# DAC_1CH.net
KiCad netlist of a schematic drawn in Altium Designer
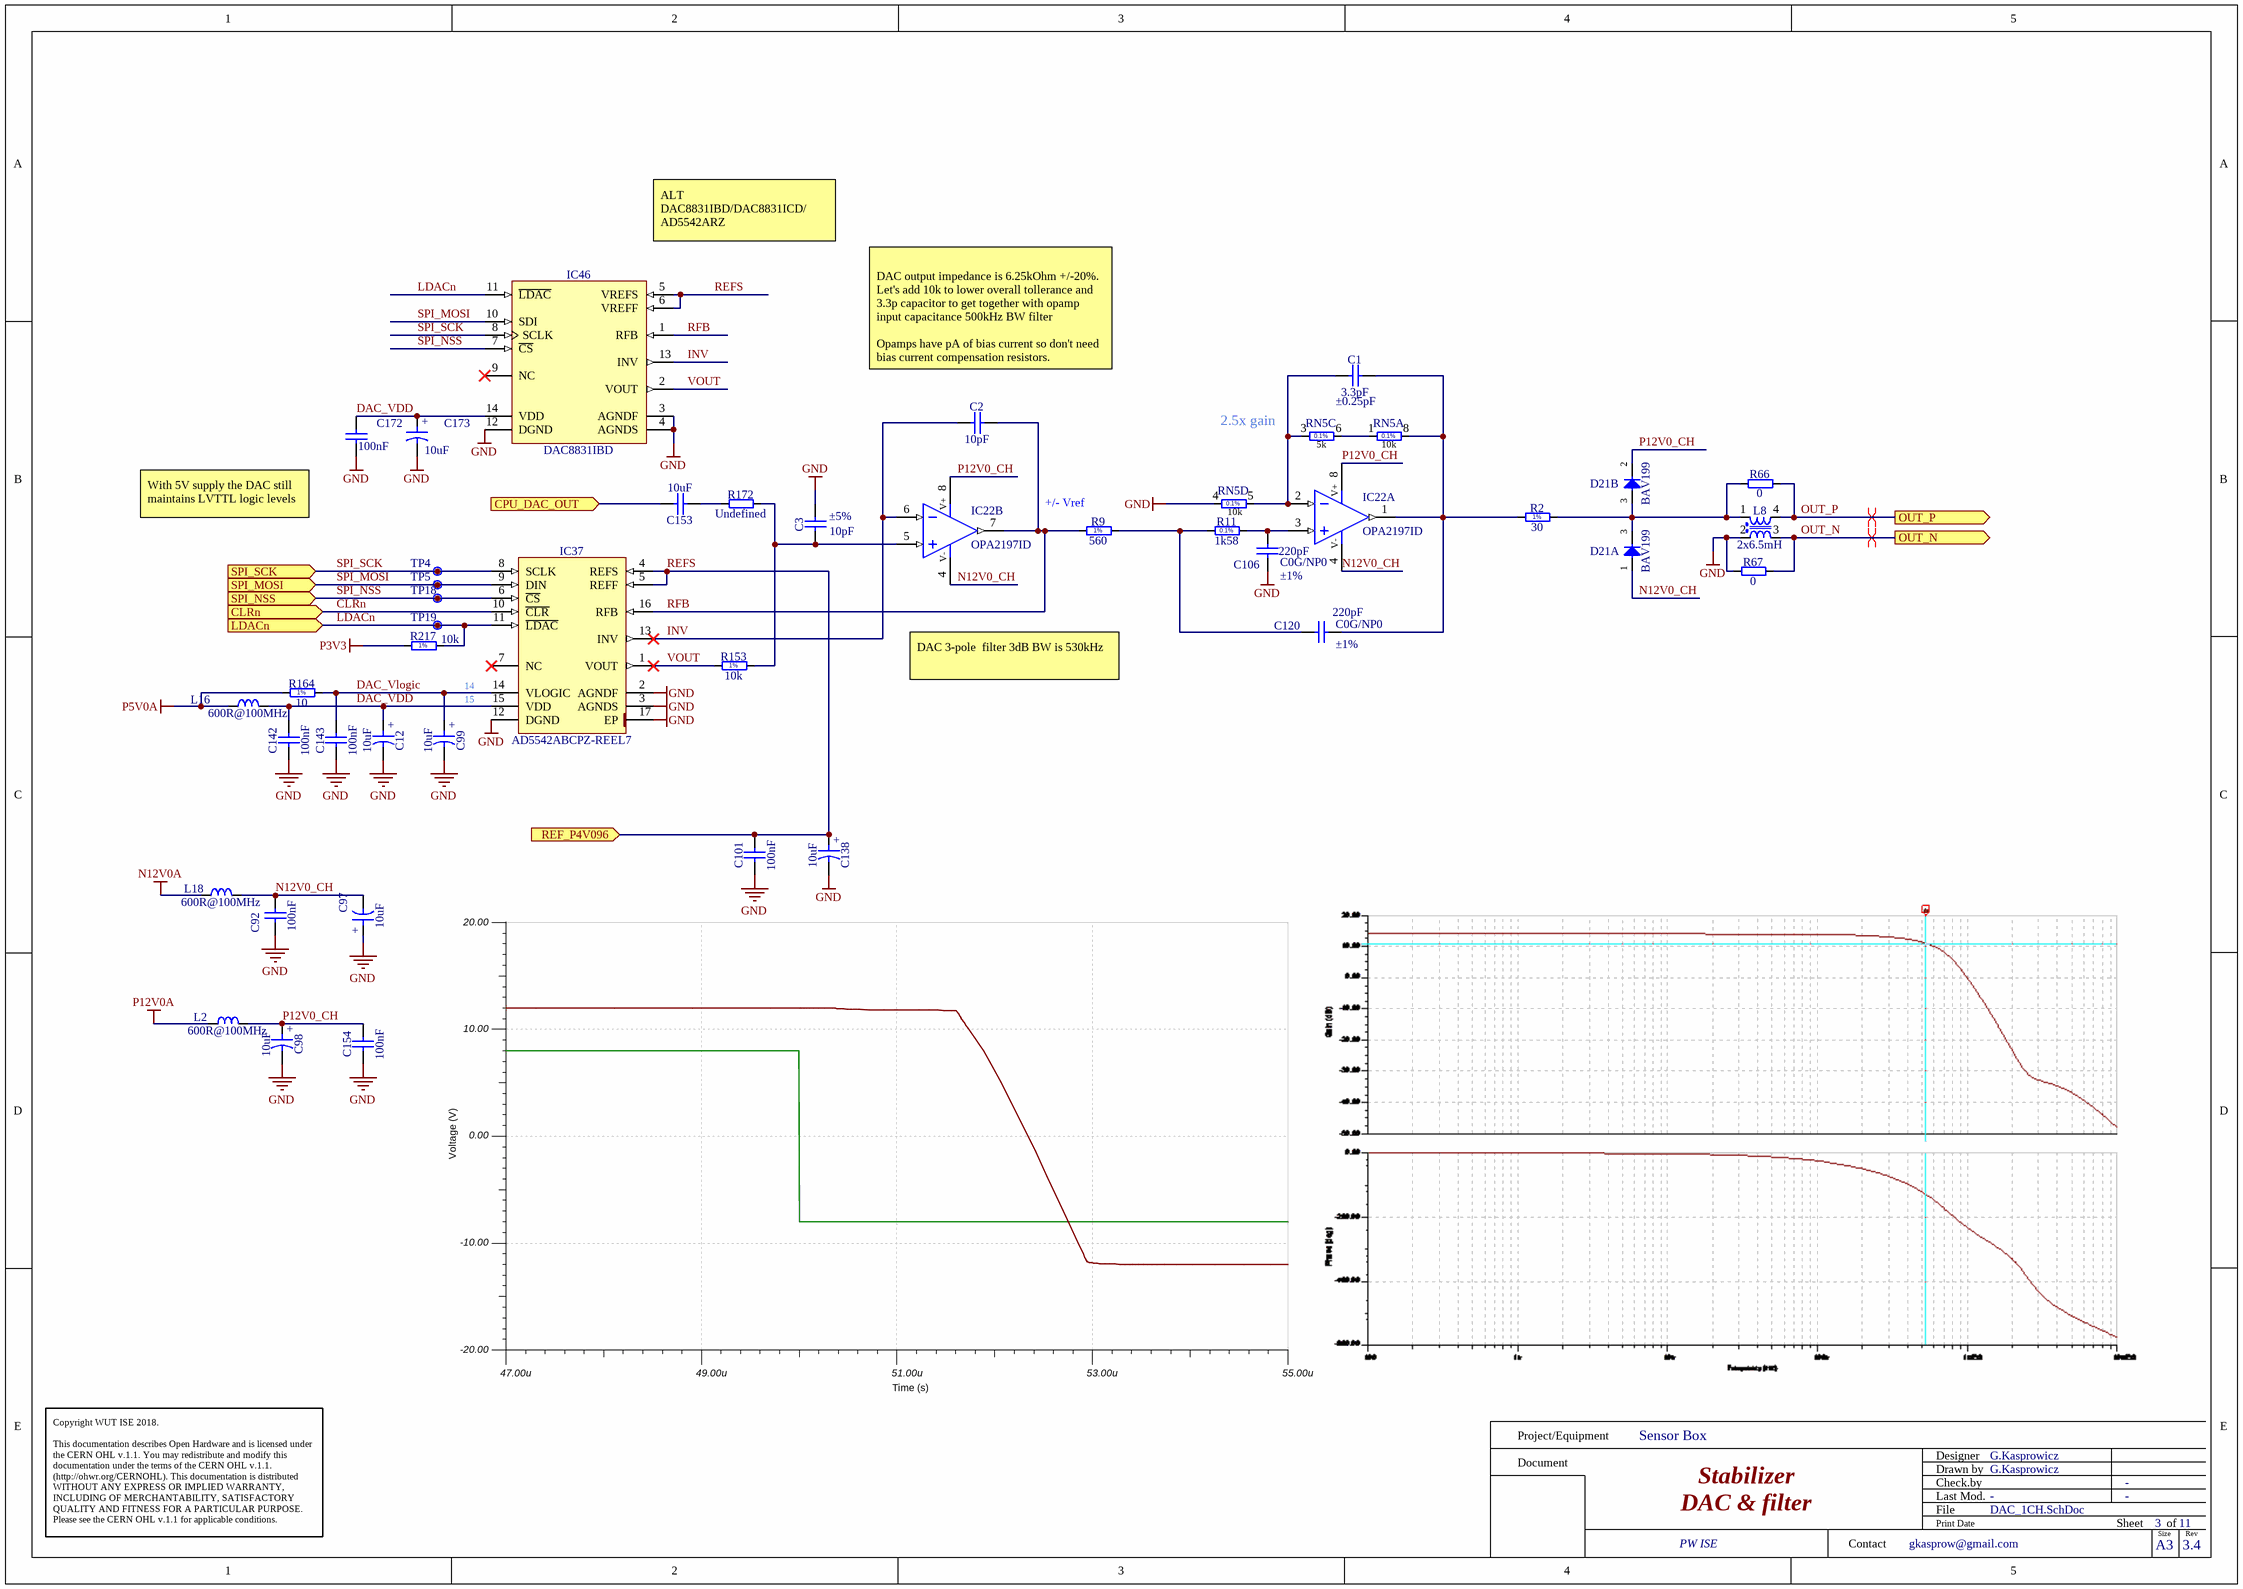
[diagram p0: DAC_1CH.SchDoc]

(export (version "E")
  (design (tool "Eeschema 10.0.6"))
  (components
    (comp (ref "C1")
      (value "3.3pF")
      (footprint "CAPC1005X55N")
      (description "Non-polarised capacitor")
      (fields
        (field (name "PART NUMBER") "CC0402_3.3PF_50V_0.25PF_C0G")
        (field (name "VOLTAGE") "50V")
        (field (name "TOLERANCE") "±0.25pF")
        (field (name "AUTHOR") "CERN DEM JLC")
      )
      (libsource (lib "Capacitors") (part "Capacitor - non polarized"))
    )
    (comp (ref "C2")
      (value "10pF")
      (footprint "CAPC1005X55N")
      (description "Non-polarised capacitor")
      (fields
        (field (name "PART NUMBER") "CC0402_10PF_50V_5%_C0G")
        (field (name "VOLTAGE") "50V")
        (field (name "AUTHOR") "CERN DEM JLC")
      )
      (libsource (lib "Capacitors") (part "Capacitor - non polarized"))
    )
    (comp (ref "C3")
      (value "10pF")
      (footprint "CAPC1005X55N")
      (description "Non-polarised capacitor")
      (fields
        (field (name "PART NUMBER") "CC0402_10PF_50V_5%_C0G")
        (field (name "VOLTAGE") "50V")
        (field (name "TOLERANCE") "±5%")
        (field (name "AUTHOR") "CERN DEM JLC")
      )
      (libsource (lib "Capacitors") (part "Capacitor - non polarized"))
    )
    (comp (ref "C12")
      (value "10uF")
      (footprint "CAPMP3216X180N")
      (description "Polarised capacitor")
      (fields
        (field (name "PART NUMBER") "CTE3216-18_10UF_16V_20%_AVX_TCJ")
        (field (name "VOLTAGE") "16V")
        (field (name "AUTHOR") "CERN DEM JLC")
      )
      (libsource (lib "Capacitors") (part "Capacitor - polarized"))
    )
    (comp (ref "C92")
      (value "100nF")
      (footprint "CAPC1005X55N")
      (description "Non-polarised capacitor")
      (fields
        (field (name "PART NUMBER") "CC0402_100NF_16V_10%_X7R")
        (field (name "VOLTAGE") "16V")
        (field (name "AUTHOR") "CERN DEM JLC")
      )
      (libsource (lib "Capacitors") (part "Capacitor - non polarized"))
    )
    (comp (ref "C97")
      (value "10uF")
      (footprint "CAPMP3216X180N")
      (description "Polarised capacitor")
      (fields
        (field (name "PART NUMBER") "CTE3216-18_10UF_16V_20%_AVX_TCJ")
        (field (name "VOLTAGE") "16V")
        (field (name "AUTHOR") "CERN DEM JLC")
      )
      (libsource (lib "Capacitors") (part "Capacitor - polarized"))
    )
    (comp (ref "C98")
      (value "10uF")
      (footprint "CAPMP3216X180N")
      (description "Polarised capacitor")
      (fields
        (field (name "PART NUMBER") "CTE3216-18_10UF_16V_20%_AVX_TCJ")
        (field (name "VOLTAGE") "16V")
        (field (name "AUTHOR") "CERN DEM JLC")
      )
      (libsource (lib "Capacitors") (part "Capacitor - polarized"))
    )
    (comp (ref "C99")
      (value "10uF")
      (footprint "CAPMP3216X180N")
      (description "Polarised capacitor")
      (fields
        (field (name "PART NUMBER") "CTE3216-18_10UF_16V_20%_AVX_TCJ")
        (field (name "VOLTAGE") "16V")
        (field (name "AUTHOR") "CERN DEM JLC")
      )
      (libsource (lib "Capacitors") (part "Capacitor - polarized"))
    )
    (comp (ref "C101")
      (value "100nF")
      (footprint "CAPC1005X55N")
      (description "Non-polarised capacitor")
      (fields
        (field (name "PART NUMBER") "CC0402_100NF_16V_10%_X7R")
        (field (name "VOLTAGE") "16V")
        (field (name "AUTHOR") "CERN DEM JLC")
      )
      (libsource (lib "Capacitors") (part "Capacitor - non polarized"))
    )
    (comp (ref "C106")
      (value "220pF")
      (footprint "CAPC2013X100N")
      (description "Non-polarised capacitor")
      (fields
        (field (name "PART NUMBER") "CC0805_220PF_25V_1%_C0G")
        (field (name "VOLTAGE") "25V")
        (field (name "TC") "C0G/NP0")
        (field (name "TOLERANCE") "±1%")
        (field (name "AUTHOR") "CERN DEM JLC")
      )
      (libsource (lib "Capacitors") (part "Capacitor - non polarized"))
    )
    (comp (ref "C120")
      (value "220pF")
      (footprint "CAPC2013X100N")
      (description "Non-polarised capacitor")
      (fields
        (field (name "PART NUMBER") "CC0805_220PF_25V_1%_C0G")
        (field (name "VOLTAGE") "25V")
        (field (name "TC") "C0G/NP0")
        (field (name "TOLERANCE") "±1%")
        (field (name "AUTHOR") "CERN DEM JLC")
      )
      (libsource (lib "Capacitors") (part "Capacitor - non polarized"))
    )
    (comp (ref "C138")
      (value "10uF")
      (footprint "CAPMP3216X180N")
      (description "Polarised capacitor")
      (fields
        (field (name "PART NUMBER") "CTE3216-18_10UF_16V_20%_AVX_TCJ")
        (field (name "VOLTAGE") "16V")
        (field (name "AUTHOR") "CERN DEM JLC")
      )
      (libsource (lib "Capacitors") (part "Capacitor - polarized"))
    )
    (comp (ref "C142")
      (value "100nF")
      (footprint "CAPC1005X55N")
      (description "Non-polarised capacitor")
      (fields
        (field (name "PART NUMBER") "CC0402_100NF_16V_10%_X7R")
        (field (name "VOLTAGE") "16V")
        (field (name "AUTHOR") "CERN DEM JLC")
      )
      (libsource (lib "Capacitors") (part "Capacitor - non polarized"))
    )
    (comp (ref "C143")
      (value "100nF")
      (footprint "CAPC1005X55N")
      (description "Non-polarised capacitor")
      (fields
        (field (name "PART NUMBER") "CC0402_100NF_16V_10%_X7R")
        (field (name "VOLTAGE") "16V")
        (field (name "AUTHOR") "CERN DEM JLC")
      )
      (libsource (lib "Capacitors") (part "Capacitor - non polarized"))
    )
    (comp (ref "C153")
      (value "10uF")
      (footprint "CAPC2012X95N")
      (description "Non-polarised capacitor")
      (fields
        (field (name "PART NUMBER") "CC0805_10UF_25V_10%_X5R")
        (field (name "VOLTAGE") "25V")
        (field (name "AUTHOR") "CERN DEM JLC")
      )
      (libsource (lib "Capacitors") (part "Capacitor - non polarized"))
    )
    (comp (ref "C154")
      (value "100nF")
      (footprint "CAPC1005X55N")
      (description "Non-polarised capacitor")
      (fields
        (field (name "PART NUMBER") "CC0402_100NF_16V_10%_X7R")
        (field (name "VOLTAGE") "16V")
        (field (name "AUTHOR") "CERN DEM JLC")
      )
      (libsource (lib "Capacitors") (part "Capacitor - non polarized"))
    )
    (comp (ref "C172")
      (value "100nF")
      (footprint "CAPC1005X55N")
      (description "Non-polarised capacitor")
      (fields
        (field (name "PART NUMBER") "CC0402_100NF_16V_10%_X7R")
        (field (name "VOLTAGE") "16V")
        (field (name "AUTHOR") "CERN DEM JLC")
      )
      (libsource (lib "Capacitors") (part "Capacitor - non polarized"))
    )
    (comp (ref "C173")
      (value "10uF")
      (footprint "CAPMP3216X180N")
      (description "Polarised capacitor")
      (fields
        (field (name "PART NUMBER") "CTE3216-18_10UF_16V_20%_AVX_TCJ")
        (field (name "VOLTAGE") "16V")
        (field (name "AUTHOR") "CERN DEM JLC")
      )
      (libsource (lib "Capacitors") (part "Capacitor - polarized"))
    )
    (comp (ref "D21")
      (value "BAV199")
      (footprint "SOT95P240X110-3N")
      (description "Serial Diode")
      (fields
        (field (name "VOLTAGE") "75V")
        (field (name "POWER") "250mW")
        (field (name "AUTHOR") "CERN DEM JMW")
      )
      (libsource (lib "ICs And Semiconductors") (part "Diode x2 A1C3_A3C2"))
    )
    (comp (ref "IC22")
      (value "OPA2197ID")
      (footprint "SOIC127P600X175-8N")
      (description "Dual Operational Amplifier")
      (fields (field (name "MANUFACTURER") "TEXAS INSTRUMENTS") (field (name "AUTHOR") "CERN DEM MR"))
      (libsource (lib "ICs And Semiconductors") (part "Operational Amplifier x2 Type1"))
    )
    (comp (ref "IC37")
      (value "AD5542ABCPZ-REEL7")
      (footprint "QFN50P300X300X80-17N-S175")
      (description "2.7V to 5.5V, Serial-Input, Voltage-Output, 16-Bit DAC")
      (fields (field (name "MANUFACTURER") "ANALOG DEVICES") (field (name "AUTHOR") "CERN DEM JLC"))
      (libsource (lib "ICs And Semiconductors") (part "AD5542ABCPZ"))
    )
    (comp (ref "IC46")
      (value "DAC8831IBD")
      (footprint "SOIC127P600X175-14N")
      (description "16-Bit, Ultra-Low Power, Voltage-Output Digital-to-Analog Converter")
      (fields (field (name "MANUFACTURER") "TEXAS INSTRUMENTS") (field (name "AUTHOR") "GK"))
      (libsource (lib "ICs And Semiconductors") (part "DAC8831ICD"))
    )
    (comp (ref "L2")
      (value "600R@100MHz")
      (footprint "INDC1005X55N")
      (description "Inductor")
      (fields
        (field (name "PART NUMBER") "IND0402_MURATA_BLM15HD601SN1")
        (field (name "POWER") "300mA")
        (field (name "AUTHOR") "CERN DEM JLC")
      )
      (libsource (lib "Inductors & Transformers") (part "Inductor"))
    )
    (comp (ref "L8")
      (value "2x6.5mH")
      (footprint "IND_WURTH_WE-SL2")
      (description "Inductor Common Mode")
      (fields
        (field (name "PART NUMBER") "IND_6.5MH_50%_WURTH_WE-SL2-744229")
        (field (name "POWER") "400mA")
        (field (name "AUTHOR") "CERN DEM JLC")
      )
      (libsource (lib "Inductors & Transformers") (part "Inductor Common Mode 1Dot-4 2Dot-3"))
    )
    (comp (ref "L16")
      (value "600R@100MHz")
      (footprint "INDC1005X55N")
      (description "Inductor")
      (fields
        (field (name "PART NUMBER") "IND0402_MURATA_BLM15HD601SN1")
        (field (name "POWER") "300mA")
        (field (name "AUTHOR") "CERN DEM JLC")
      )
      (libsource (lib "Inductors & Transformers") (part "Inductor"))
    )
    (comp (ref "L18")
      (value "600R@100MHz")
      (footprint "INDC1005X55N")
      (description "Inductor")
      (fields
        (field (name "PART NUMBER") "IND0402_MURATA_BLM15HD601SN1")
        (field (name "POWER") "300mA")
        (field (name "AUTHOR") "CERN DEM JLC")
      )
      (libsource (lib "Inductors & Transformers") (part "Inductor"))
    )
    (comp (ref "R2")
      (value "30")
      (footprint "RESC1608X55N")
      (description "Resistor - 1%")
      (fields
        (field (name "PART NUMBER") "R0603_30R_1%_0.1W_100PPM")
        (field (name "POWER") "0.1W")
        (field (name "AUTHOR") "CERN DEM JLC")
      )
      (libsource (lib "Resistors") (part "Resistor - 1%"))
    )
    (comp (ref "R9")
      (value "560")
      (footprint "RESC1608X55N")
      (description "Resistor - 1%")
      (fields
        (field (name "PART NUMBER") "R0603_560R_1%_0.1W_100PPM")
        (field (name "POWER") "0.1W")
        (field (name "AUTHOR") "CERN DEM JLC")
      )
      (libsource (lib "Resistors") (part "Resistor - 1%"))
    )
    (comp (ref "R11")
      (value "1k58")
      (footprint "RESC1608X55N")
      (description "Resistor - 0.1%")
      (fields
        (field (name "PART NUMBER") "R0603_1K58_0.1%_0.063W_10PPM")
        (field (name "POWER") "0.063W")
        (field (name "AUTHOR") "CERN DEM JLC")
      )
      (libsource (lib "Resistors") (part "Resistor - 0.1%"))
    )
    (comp (ref "R66")
      (value "0")
      (footprint "RESC1608X55N")
      (description "Resistor")
      (fields
        (field (name "PART NUMBER") "R0603_0R_JUMPER")
        (field (name "MANUFACTURER") "GENERIC")
        (field (name "AUTHOR") "CERN DEM JLC")
      )
      (libsource (lib "Resistors") (part "Resistor"))
    )
    (comp (ref "R67")
      (value "0")
      (footprint "RESC1608X55N")
      (description "Resistor")
      (fields
        (field (name "PART NUMBER") "R0603_0R_JUMPER")
        (field (name "MANUFACTURER") "GENERIC")
        (field (name "AUTHOR") "CERN DEM JLC")
      )
      (libsource (lib "Resistors") (part "Resistor"))
    )
    (comp (ref "R153")
      (value "10k")
      (footprint "RESC1005X40N")
      (description "Resistor - 1%")
      (fields
        (field (name "PART NUMBER") "R0402_10K_1%_0.0625W_100PPM")
        (field (name "POWER") "0.0625W")
        (field (name "AUTHOR") "CERN DEM JLC")
      )
      (libsource (lib "Resistors") (part "Resistor - 1%"))
    )
    (comp (ref "R164")
      (value "10")
      (footprint "RESC1005X40N")
      (description "Resistor - 1%")
      (fields
        (field (name "PART NUMBER") "R0402_10R_1%_0.0625W_200PPM")
        (field (name "POWER") "0.0625W")
        (field (name "AUTHOR") "CERN DEM JLC")
      )
      (libsource (lib "Resistors") (part "Resistor - 1%"))
    )
    (comp (ref "R172")
      (value "Undefined")
      (footprint "RESC1608X55N")
      (description "Resistor")
      (fields (field (name "PART NUMBER") "R0603_NO-VALUE") (field (name "AUTHOR") "CERN DEM JLC"))
      (libsource (lib "Resistors") (part "Resistor"))
    )
    (comp (ref "R217")
      (value "10k")
      (footprint "RESC1005X40N")
      (description "Resistor - 1%")
      (fields
        (field (name "PART NUMBER") "R0402_10K_1%_0.0625W_100PPM")
        (field (name "POWER") "0.0625W")
        (field (name "AUTHOR") "CERN DEM JLC")
      )
      (libsource (lib "Resistors") (part "Resistor - 1%"))
    )
    (comp (ref "RN5")
      (value "10k 5K 5K 10K")
      (footprint "SOIC127P600X175-8N")
      (description "DIL8 Resistor Network 4 Resistors 10k-5k-5k-10k 0.1%")
      (fields
        (field (name "PART NUMBER") "RN_10K_5K_VISHAY_AORN2-1AT3")
        (field (name "POWER") "4x0.1W")
        (field (name "AUTHOR") "CERN DEM JLC")
      )
      (libsource (lib "Resistors") (part "RN DIL8_4xR_10k-5k-5k-10k_0.1%"))
    )
    (comp (ref "TP4")
      (value "Test Point")
      (footprint "TPS127")
      (fields (field (name "PART NUMBER") "SMD_PAD_1.27X1.27MM") (field (name "AUTHOR") "CERN DEM JLC"))
      (libsource (lib "Eletro-mechanical") (part "Test Point"))
    )
    (comp (ref "TP5")
      (value "Test Point")
      (footprint "TPS127")
      (fields (field (name "PART NUMBER") "SMD_PAD_1.27X1.27MM") (field (name "AUTHOR") "CERN DEM JLC"))
      (libsource (lib "Eletro-mechanical") (part "Test Point"))
    )
    (comp (ref "TP18")
      (value "Test Point")
      (footprint "TPS127")
      (fields (field (name "PART NUMBER") "SMD_PAD_1.27X1.27MM") (field (name "AUTHOR") "CERN DEM JLC"))
      (libsource (lib "Eletro-mechanical") (part "Test Point"))
    )
    (comp (ref "TP19")
      (value "Test Point")
      (footprint "TPS127")
      (fields (field (name "PART NUMBER") "SMD_PAD_1.27X1.27MM") (field (name "AUTHOR") "CERN DEM JLC"))
      (libsource (lib "Eletro-mechanical") (part "Test Point"))
    )
  )
  (nets
    (net (code "1") (name "/CLRn") (class "Default")
      (node (ref "IC37") (pin "10") (pinfunction "~{CLR}_10") (pintype "input"))
    )
    (net (code "2") (name "/CPU_DAC_OUT") (class "Default")
      (node (ref "C153") (pin "2") (pinfunction "2_2") (pintype "passive"))
    )
    (net (code "3") (name "/DAC_VDD") (class "Default")
      (node (ref "C12") (pin "1") (pinfunction "1_1") (pintype "passive"))
      (node (ref "C142") (pin "2") (pinfunction "2_2") (pintype "passive"))
      (node (ref "C172") (pin "2") (pinfunction "2_2") (pintype "passive"))
      (node (ref "C173") (pin "1") (pinfunction "1_1") (pintype "passive"))
      (node (ref "IC37") (pin "15") (pinfunction "VDD_15") (pintype "power_in"))
      (node (ref "IC46") (pin "14") (pinfunction "VDD_14") (pintype "power_in"))
      (node (ref "L16") (pin "2") (pinfunction "2_2") (pintype "passive"))
    )
    (net (code "4") (name "/DAC_Vlogic") (class "Default")
      (node (ref "C143") (pin "2") (pinfunction "2_2") (pintype "passive"))
      (node (ref "C99") (pin "1") (pinfunction "1_1") (pintype "passive"))
      (node (ref "IC37") (pin "14") (pinfunction "VLOGIC_14") (pintype "power_in"))
      (node (ref "R164") (pin "2") (pinfunction "2_2") (pintype "passive"))
    )
    (net (code "5") (name "/INV") (class "Default")
      (node (ref "C2") (pin "1") (pinfunction "1_1") (pintype "passive"))
      (node (ref "IC22") (pin "6") (pinfunction "IN-_6") (pintype "input"))
      (node (ref "IC37") (pin "13") (pinfunction "INV_13") (pintype "output"))
      (node (ref "IC46") (pin "13") (pinfunction "INV_13") (pintype "output"))
    )
    (net (code "6") (name "/LDACn") (class "Default")
      (node (ref "IC37") (pin "11") (pinfunction "~{LDAC}_11") (pintype "input"))
      (node (ref "IC46") (pin "11") (pinfunction "~{LDAC}_11") (pintype "input"))
      (node (ref "R217") (pin "2") (pinfunction "2_2") (pintype "passive"))
      (node (ref "TP19") (pin "1") (pinfunction "1_1") (pintype "bidirectional"))
    )
    (net (code "7") (name "/N12V0_CH") (class "Default")
      (node (ref "C92") (pin "2") (pinfunction "2_2") (pintype "passive"))
      (node (ref "C97") (pin "2") (pinfunction "2_2") (pintype "passive"))
      (node (ref "D21") (pin "1") (pinfunction "A_1") (pintype "passive"))
      (node (ref "IC22") (pin "4") (pinfunction "V-_4") (pintype "power_in"))
      (node (ref "L18") (pin "2") (pinfunction "2_2") (pintype "passive"))
    )
    (net (code "8") (name "/OUT_N") (class "Default")
      (node (ref "L8") (pin "3") (pinfunction "3_3") (pintype "passive"))
      (node (ref "R67") (pin "2") (pinfunction "2_2") (pintype "passive"))
    )
    (net (code "9") (name "/OUT_P") (class "Default")
      (node (ref "L8") (pin "4") (pinfunction "4_4") (pintype "passive"))
      (node (ref "R66") (pin "2") (pinfunction "2_2") (pintype "passive"))
    )
    (net (code "10") (name "/P12V0_CH") (class "Default")
      (node (ref "C154") (pin "2") (pinfunction "2_2") (pintype "passive"))
      (node (ref "C98") (pin "1") (pinfunction "1_1") (pintype "passive"))
      (node (ref "D21") (pin "2") (pinfunction "C_2") (pintype "passive"))
      (node (ref "IC22") (pin "8") (pinfunction "V+_8") (pintype "power_in"))
      (node (ref "L2") (pin "2") (pinfunction "2_2") (pintype "passive"))
    )
    (net (code "11") (name "/REFS") (class "Default")
      (node (ref "C101") (pin "2") (pinfunction "2_2") (pintype "passive"))
      (node (ref "C138") (pin "1") (pinfunction "1_1") (pintype "passive"))
      (node (ref "IC37") (pin "4") (pinfunction "REFS_4") (pintype "input"))
      (node (ref "IC37") (pin "5") (pinfunction "REFF_5") (pintype "input"))
      (node (ref "IC46") (pin "5") (pinfunction "VREFS_5") (pintype "input"))
      (node (ref "IC46") (pin "6") (pinfunction "VREFF_6") (pintype "input"))
    )
    (net (code "12") (name "/RFB") (class "Default")
      (node (ref "C2") (pin "2") (pinfunction "2_2") (pintype "passive"))
      (node (ref "IC22") (pin "7") (pinfunction "OUT_7") (pintype "output"))
      (node (ref "IC37") (pin "16") (pinfunction "RFB_16") (pintype "input"))
      (node (ref "IC46") (pin "1") (pinfunction "RFB_1") (pintype "input"))
      (node (ref "R9") (pin "1") (pinfunction "1_1") (pintype "passive"))
    )
    (net (code "13") (name "/SPI_MOSI") (class "Default")
      (node (ref "IC37") (pin "9") (pinfunction "DIN_9") (pintype "input"))
      (node (ref "IC46") (pin "10") (pinfunction "SDI_10") (pintype "input"))
      (node (ref "TP5") (pin "1") (pinfunction "1_1") (pintype "bidirectional"))
    )
    (net (code "14") (name "/SPI_NSS") (class "Default")
      (node (ref "IC37") (pin "6") (pinfunction "~{CS}_6") (pintype "input"))
      (node (ref "IC46") (pin "7") (pinfunction "~{CS}_7") (pintype "input"))
      (node (ref "TP18") (pin "1") (pinfunction "1_1") (pintype "bidirectional"))
    )
    (net (code "15") (name "/SPI_SCK") (class "Default")
      (node (ref "IC37") (pin "8") (pinfunction "SCLK_8") (pintype "input"))
      (node (ref "IC46") (pin "8") (pinfunction "SCLK_8") (pintype "input"))
      (node (ref "TP4") (pin "1") (pinfunction "1_1") (pintype "bidirectional"))
    )
    (net (code "16") (name "/VOUT") (class "Default")
      (node (ref "IC37") (pin "1") (pinfunction "VOUT_1") (pintype "output"))
      (node (ref "IC46") (pin "2") (pinfunction "VOUT_2") (pintype "output"))
      (node (ref "R153") (pin "1") (pinfunction "1_1") (pintype "passive"))
    )
    (net (code "17") (name "GND") (class "Default")
      (node (ref "C101") (pin "1") (pinfunction "1_1") (pintype "passive"))
      (node (ref "C106") (pin "1") (pinfunction "1_1") (pintype "passive"))
      (node (ref "C12") (pin "2") (pinfunction "2_2") (pintype "passive"))
      (node (ref "C138") (pin "2") (pinfunction "2_2") (pintype "passive"))
      (node (ref "C142") (pin "1") (pinfunction "1_1") (pintype "passive"))
      (node (ref "C143") (pin "1") (pinfunction "1_1") (pintype "passive"))
      (node (ref "C154") (pin "1") (pinfunction "1_1") (pintype "passive"))
      (node (ref "C172") (pin "1") (pinfunction "1_1") (pintype "passive"))
      (node (ref "C173") (pin "2") (pinfunction "2_2") (pintype "passive"))
      (node (ref "C3") (pin "2") (pinfunction "2_2") (pintype "passive"))
      (node (ref "C92") (pin "1") (pinfunction "1_1") (pintype "passive"))
      (node (ref "C97") (pin "1") (pinfunction "1_1") (pintype "passive"))
      (node (ref "C98") (pin "2") (pinfunction "2_2") (pintype "passive"))
      (node (ref "C99") (pin "2") (pinfunction "2_2") (pintype "passive"))
      (node (ref "IC37") (pin "12") (pinfunction "DGND_12") (pintype "power_in"))
      (node (ref "IC37") (pin "17") (pinfunction "EP_17") (pintype "power_in"))
      (node (ref "IC37") (pin "2") (pinfunction "AGNDF_2") (pintype "power_in"))
      (node (ref "IC37") (pin "3") (pinfunction "AGNDS_3") (pintype "power_in"))
      (node (ref "IC46") (pin "12") (pinfunction "DGND_12") (pintype "power_in"))
      (node (ref "IC46") (pin "3") (pinfunction "AGNDF_3") (pintype "power_in"))
      (node (ref "IC46") (pin "4") (pinfunction "AGNDS_4") (pintype "power_in"))
      (node (ref "L8") (pin "2") (pinfunction "2_2") (pintype "passive"))
      (node (ref "R67") (pin "1") (pinfunction "1_1") (pintype "passive"))
      (node (ref "RN5") (pin "4") (pinfunction "4_4") (pintype "passive"))
    )
    (net (code "18") (name "N12V0A") (class "Default")
      (node (ref "L18") (pin "1") (pinfunction "1_1") (pintype "passive"))
    )
    (net (code "19") (name "Net-(C120-Pad1)") (class "Default")
      (node (ref "C120") (pin "1") (pinfunction "1_1") (pintype "passive"))
      (node (ref "R11") (pin "1") (pinfunction "1_1") (pintype "passive"))
      (node (ref "R9") (pin "2") (pinfunction "2_2") (pintype "passive"))
    )
    (net (code "20") (name "Net-(C153-Pad1)") (class "Default")
      (node (ref "C153") (pin "1") (pinfunction "1_1") (pintype "passive"))
      (node (ref "R172") (pin "1") (pinfunction "1_1") (pintype "passive"))
    )
    (net (code "21") (name "Net-(D21A-COMAC)") (class "Default")
      (node (ref "D21") (pin "3") (pinfunction "COMAC_3") (pintype "passive"))
      (node (ref "L8") (pin "1") (pinfunction "1_1") (pintype "passive"))
      (node (ref "R2") (pin "2") (pinfunction "2_2") (pintype "passive"))
      (node (ref "R66") (pin "1") (pinfunction "1_1") (pintype "passive"))
    )
    (net (code "22") (name "Net-(IC22A-IN+)") (class "Default")
      (node (ref "C106") (pin "2") (pinfunction "2_2") (pintype "passive"))
      (node (ref "IC22") (pin "3") (pinfunction "IN+_3") (pintype "input"))
      (node (ref "R11") (pin "2") (pinfunction "2_2") (pintype "passive"))
    )
    (net (code "23") (name "Net-(IC22A-IN-)") (class "Default")
      (node (ref "C1") (pin "1") (pinfunction "1_1") (pintype "passive"))
      (node (ref "IC22") (pin "2") (pinfunction "IN-_2") (pintype "input"))
      (node (ref "RN5") (pin "3") (pinfunction "3_3") (pintype "passive"))
      (node (ref "RN5") (pin "5") (pinfunction "5_5") (pintype "passive"))
    )
    (net (code "24") (name "Net-(IC22A-OUT)") (class "Default")
      (node (ref "C1") (pin "2") (pinfunction "2_2") (pintype "passive"))
      (node (ref "C120") (pin "2") (pinfunction "2_2") (pintype "passive"))
      (node (ref "IC22") (pin "1") (pinfunction "OUT_1") (pintype "output"))
      (node (ref "R2") (pin "1") (pinfunction "1_1") (pintype "passive"))
      (node (ref "RN5") (pin "8") (pinfunction "8_8") (pintype "passive"))
    )
    (net (code "25") (name "Net-(IC22B-IN+)") (class "Default")
      (node (ref "C3") (pin "1") (pinfunction "1_1") (pintype "passive"))
      (node (ref "IC22") (pin "5") (pinfunction "IN+_5") (pintype "input"))
      (node (ref "R153") (pin "2") (pinfunction "2_2") (pintype "passive"))
      (node (ref "R172") (pin "2") (pinfunction "2_2") (pintype "passive"))
    )
    (net (code "26") (name "Net-(RN5-Pad1)") (class "Default")
      (node (ref "RN5") (pin "1") (pinfunction "1_1") (pintype "passive"))
      (node (ref "RN5") (pin "6") (pinfunction "6_6") (pintype "passive"))
    )
    (net (code "27") (name "P3V3") (class "Default")
      (node (ref "R217") (pin "1") (pinfunction "1_1") (pintype "passive"))
    )
    (net (code "28") (name "P5V0A") (class "Default")
      (node (ref "L16") (pin "1") (pinfunction "1_1") (pintype "passive"))
      (node (ref "R164") (pin "1") (pinfunction "1_1") (pintype "passive"))
    )
    (net (code "29") (name "P12V0A") (class "Default")
      (node (ref "L2") (pin "1") (pinfunction "1_1") (pintype "passive"))
    )
    (net (code "30") (name "unconnected-(IC37-NC-Pad7)") (class "Default")
      (node (ref "IC37") (pin "7") (pinfunction "NC_7") (pintype "passive+no_connect"))
    )
    (net (code "31") (name "unconnected-(IC46-NC-Pad9)") (class "Default")
      (node (ref "IC46") (pin "9") (pinfunction "NC_9") (pintype "passive+no_connect"))
    )
  )
)
